# arduino_power_supply.net
KiCad netlist of a schematic drawn in EAGLE
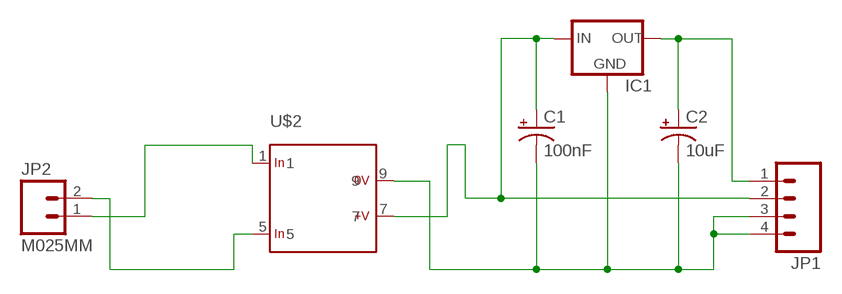
[diagram p0: schematic, sheet 1]

(export (version "E")
  (design (tool "Eeschema 10.0.6"))
  (components
    (comp (ref "C1")
      (value "100nF")
      (footprint "eagle-import:CPOL-RADIAL-10UF-25V")
      (libsource (lib "eagle-import") (part "CAP_POLPTH2"))
    )
    (comp (ref "C2")
      (value "10uF")
      (footprint "eagle-import:CPOL-RADIAL-10UF-25V")
      (libsource (lib "eagle-import") (part "CAP_POLPTH2"))
    )
    (comp (ref "IC1")
      (value "78XXS")
      (footprint "eagle-import:78XXS")
      (libsource (lib "eagle-import") (part "78XXS"))
    )
    (comp (ref "JP1")
      (value "M04PTH")
      (footprint "eagle-import:1X04")
      (libsource (lib "eagle-import") (part "M04PTH"))
    )
    (comp (ref "JP2")
      (value "M025MM")
      (footprint "eagle-import:SCREWTERMINAL-5MM-2")
      (libsource (lib "eagle-import") (part "M025MM"))
    )
    (comp (ref "U$2")
      (value "SINGLE")
      (footprint "eagle-import:1")
      (libsource (lib "eagle-import") (part "SINGLE"))
    )
  )
  (nets
    (net (code "1") (name "Net-(C1-+)") (class "Default")
      (node (ref "C1") (pin "1") (pinfunction "+_1") (pintype "passive"))
      (node (ref "IC1") (pin "IN") (pinfunction "IN_IN") (pintype "input"))
      (node (ref "JP1") (pin "2") (pinfunction "2_2") (pintype "passive"))
      (node (ref "U$2") (pin "7") (pinfunction "7_7") (pintype "output"))
    )
    (net (code "2") (name "Net-(C1--)") (class "Default")
      (node (ref "C1") (pin "2") (pinfunction "-_2") (pintype "passive"))
      (node (ref "C2") (pin "2") (pinfunction "-_2") (pintype "passive"))
      (node (ref "IC1") (pin "GND") (pinfunction "GND_GND") (pintype "input"))
      (node (ref "JP1") (pin "3") (pinfunction "3_3") (pintype "passive"))
      (node (ref "JP1") (pin "4") (pinfunction "4_4") (pintype "passive"))
      (node (ref "U$2") (pin "9") (pinfunction "9_9") (pintype "output"))
    )
    (net (code "3") (name "Net-(C2-+)") (class "Default")
      (node (ref "C2") (pin "1") (pinfunction "+_1") (pintype "passive"))
      (node (ref "IC1") (pin "OUT") (pinfunction "OUT_OUT") (pintype "passive"))
      (node (ref "JP1") (pin "1") (pinfunction "1_1") (pintype "passive"))
    )
    (net (code "4") (name "Net-(JP2-Pad1)") (class "Default")
      (node (ref "JP2") (pin "1") (pinfunction "1_1") (pintype "passive"))
      (node (ref "U$2") (pin "1") (pinfunction "1_1") (pintype "input"))
    )
    (net (code "5") (name "Net-(JP2-Pad2)") (class "Default")
      (node (ref "JP2") (pin "2") (pinfunction "2_2") (pintype "passive"))
      (node (ref "U$2") (pin "5") (pinfunction "5_5") (pintype "input"))
    )
  )
)
